# 02_ESP12_CORE.net
KiCad netlist of a schematic drawn in Altium Designer
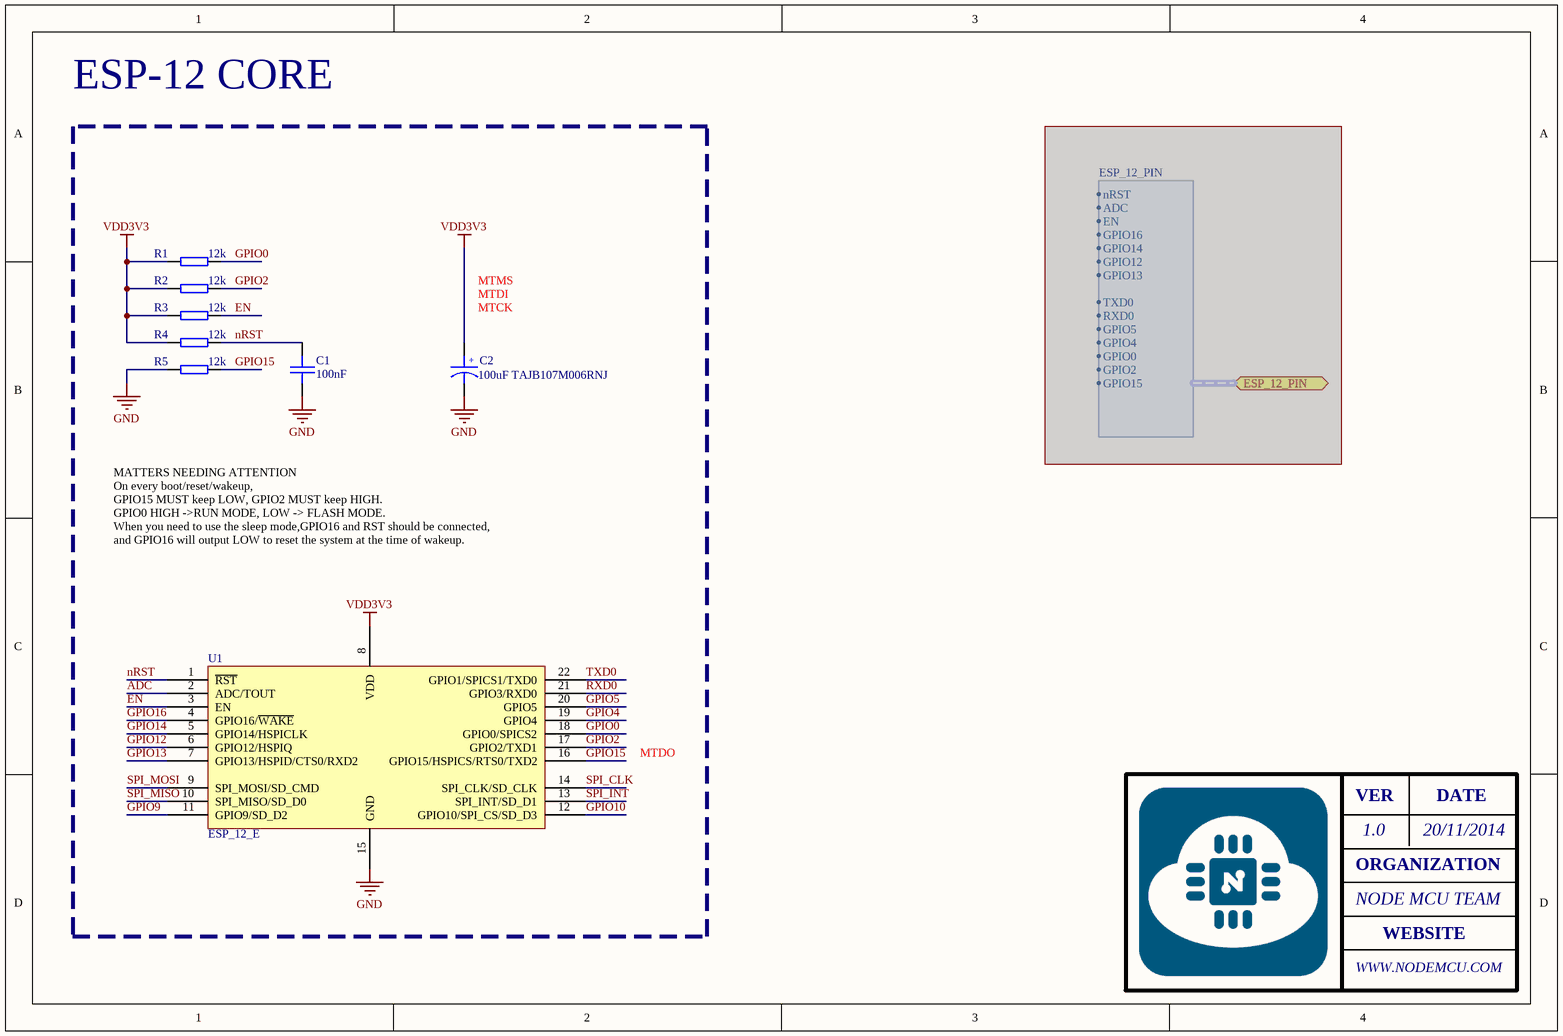
[diagram p0: 02_ESP12_CORE.SchDoc]

(export (version "E")
  (design (tool "Eeschema 10.0.6"))
  (components
    (comp (ref "C1")
      (value "100nF")
      (footprint "SMT_C_0603")
      (description "Surface mount capacitor 0402")
      (libsource (lib "Vowstar_Basic_Device") (part "SMT_C_0402"))
    )
    (comp (ref "C2")
      (value "100uF TAJB107M006RNJ")
      (footprint "SMT_C_Tantalum_B")
      (description "Capacitor, SM Tantalum; Body 3.5 x 2.8 mm (LxW typ)")
      (libsource (lib "Vowstar_Basic_Device") (part "SMT_C_Tantalum_B"))
    )
    (comp (ref "R1")
      (value "12k")
      (footprint "SMT_R_0603")
      (description "Surface mount resistor 0402")
      (libsource (lib "Vowstar_Basic_Device") (part "SMT_R_0402"))
    )
    (comp (ref "R2")
      (value "12k")
      (footprint "SMT_R_0603")
      (description "Surface mount resistor 0402")
      (libsource (lib "Vowstar_Basic_Device") (part "SMT_R_0402"))
    )
    (comp (ref "R3")
      (value "12k")
      (footprint "SMT_R_0603")
      (description "Surface mount resistor 0402")
      (libsource (lib "Vowstar_Basic_Device") (part "SMT_R_0402"))
    )
    (comp (ref "R4")
      (value "12k")
      (footprint "SMT_R_0603")
      (description "Surface mount resistor 0402")
      (libsource (lib "Vowstar_Basic_Device") (part "SMT_R_0402"))
    )
    (comp (ref "R5")
      (value "12k")
      (footprint "SMT_R_0603")
      (description "Surface mount resistor 0402")
      (libsource (lib "Vowstar_Basic_Device") (part "SMT_R_0402"))
    )
    (comp (ref "U1")
      (value "ESP_12_E")
      (footprint "ESP_12_E_L")
      (description "ESP-12 Wi-Fi Module by AI-Thinker")
      (libsource (lib "Vowstar_Module") (part "ESP_12_E"))
    )
  )
  (nets
    (net (code "2") (name "/ADC") (class "Default")
      (node (ref "U1") (pin "2") (pinfunction "ADC/TOUT_2") (pintype "passive"))
    )
    (net (code "3") (name "/EN") (class "Default")
      (node (ref "R3") (pin "2") (pinfunction "2_2") (pintype "passive"))
      (node (ref "U1") (pin "3") (pinfunction "EN_3") (pintype "passive"))
    )
    (net (code "4") (name "/GPIO0") (class "Default")
      (node (ref "R1") (pin "2") (pinfunction "2_2") (pintype "passive"))
      (node (ref "U1") (pin "18") (pinfunction "GPIO0/SPICS2_18") (pintype "passive"))
    )
    (net (code "5") (name "/GPIO2") (class "Default")
      (node (ref "R2") (pin "2") (pinfunction "2_2") (pintype "passive"))
      (node (ref "U1") (pin "17") (pinfunction "GPIO2/TXD1_17") (pintype "passive"))
    )
    (net (code "6") (name "/GPIO4") (class "Default")
      (node (ref "U1") (pin "19") (pinfunction "GPIO4_19") (pintype "passive"))
    )
    (net (code "7") (name "/GPIO5") (class "Default")
      (node (ref "U1") (pin "20") (pinfunction "GPIO5_20") (pintype "passive"))
    )
    (net (code "8") (name "/GPIO9") (class "Default")
      (node (ref "U1") (pin "11") (pinfunction "GPIO9/SD_D2_11") (pintype "passive"))
    )
    (net (code "9") (name "/GPIO10") (class "Default")
      (node (ref "U1") (pin "12") (pinfunction "GPIO10/SPI_CS/SD_D3_12") (pintype "passive"))
    )
    (net (code "10") (name "/GPIO12") (class "Default")
      (node (ref "U1") (pin "6") (pinfunction "GPIO12/HSPIQ_6") (pintype "passive"))
    )
    (net (code "11") (name "/GPIO13") (class "Default")
      (node (ref "U1") (pin "7") (pinfunction "GPIO13/HSPID/CTS0/RXD2_7") (pintype "passive"))
    )
    (net (code "12") (name "/GPIO14") (class "Default")
      (node (ref "U1") (pin "5") (pinfunction "GPIO14/HSPICLK_5") (pintype "passive"))
    )
    (net (code "13") (name "/GPIO15") (class "Default")
      (node (ref "R5") (pin "2") (pinfunction "2_2") (pintype "passive"))
      (node (ref "U1") (pin "16") (pinfunction "GPIO15/HSPICS/RTS0/TXD2_16") (pintype "passive"))
    )
    (net (code "14") (name "/GPIO16") (class "Default")
      (node (ref "U1") (pin "4") (pinfunction "GPIO16/~{WAKE}_4") (pintype "passive"))
    )
    (net (code "15") (name "/RXD0") (class "Default")
      (node (ref "U1") (pin "21") (pinfunction "GPIO3/RXD0_21") (pintype "passive"))
    )
    (net (code "16") (name "/SPI_CLK") (class "Default")
      (node (ref "U1") (pin "14") (pinfunction "SPI_CLK/SD_CLK_14") (pintype "passive"))
    )
    (net (code "17") (name "/SPI_INT") (class "Default")
      (node (ref "U1") (pin "13") (pinfunction "SPI_INT/SD_D1_13") (pintype "passive"))
    )
    (net (code "18") (name "/SPI_MISO") (class "Default")
      (node (ref "U1") (pin "10") (pinfunction "SPI_MISO/SD_D0_10") (pintype "passive"))
    )
    (net (code "19") (name "/SPI_MOSI") (class "Default")
      (node (ref "U1") (pin "9") (pinfunction "SPI_MOSI/SD_CMD_9") (pintype "passive"))
    )
    (net (code "20") (name "/TXD0") (class "Default")
      (node (ref "U1") (pin "22") (pinfunction "GPIO1/SPICS1/TXD0_22") (pintype "passive"))
    )
    (net (code "21") (name "/nRST") (class "Default")
      (node (ref "C1") (pin "1") (pinfunction "1_1") (pintype "passive"))
      (node (ref "R4") (pin "2") (pinfunction "2_2") (pintype "passive"))
      (node (ref "U1") (pin "1") (pinfunction "~{RST}_1") (pintype "passive"))
    )
    (net (code "23") (name "GND") (class "Default")
      (node (ref "C1") (pin "2") (pinfunction "2_2") (pintype "passive"))
      (node (ref "C2") (pin "2") (pinfunction "2_2") (pintype "passive"))
      (node (ref "R5") (pin "1") (pinfunction "1_1") (pintype "passive"))
      (node (ref "U1") (pin "15") (pinfunction "GND_15") (pintype "passive"))
    )
    (net (code "24") (name "VDD3V3") (class "Default")
      (node (ref "C2") (pin "1") (pinfunction "1_1") (pintype "passive"))
      (node (ref "R1") (pin "1") (pinfunction "1_1") (pintype "passive"))
      (node (ref "R2") (pin "1") (pinfunction "1_1") (pintype "passive"))
      (node (ref "R3") (pin "1") (pinfunction "1_1") (pintype "passive"))
      (node (ref "R4") (pin "1") (pinfunction "1_1") (pintype "passive"))
      (node (ref "U1") (pin "8") (pinfunction "VDD_8") (pintype "passive"))
    )
  )
)
